# DM3370_PCIE_CLK.net
KiCad netlist of a schematic drawn in Altium Designer
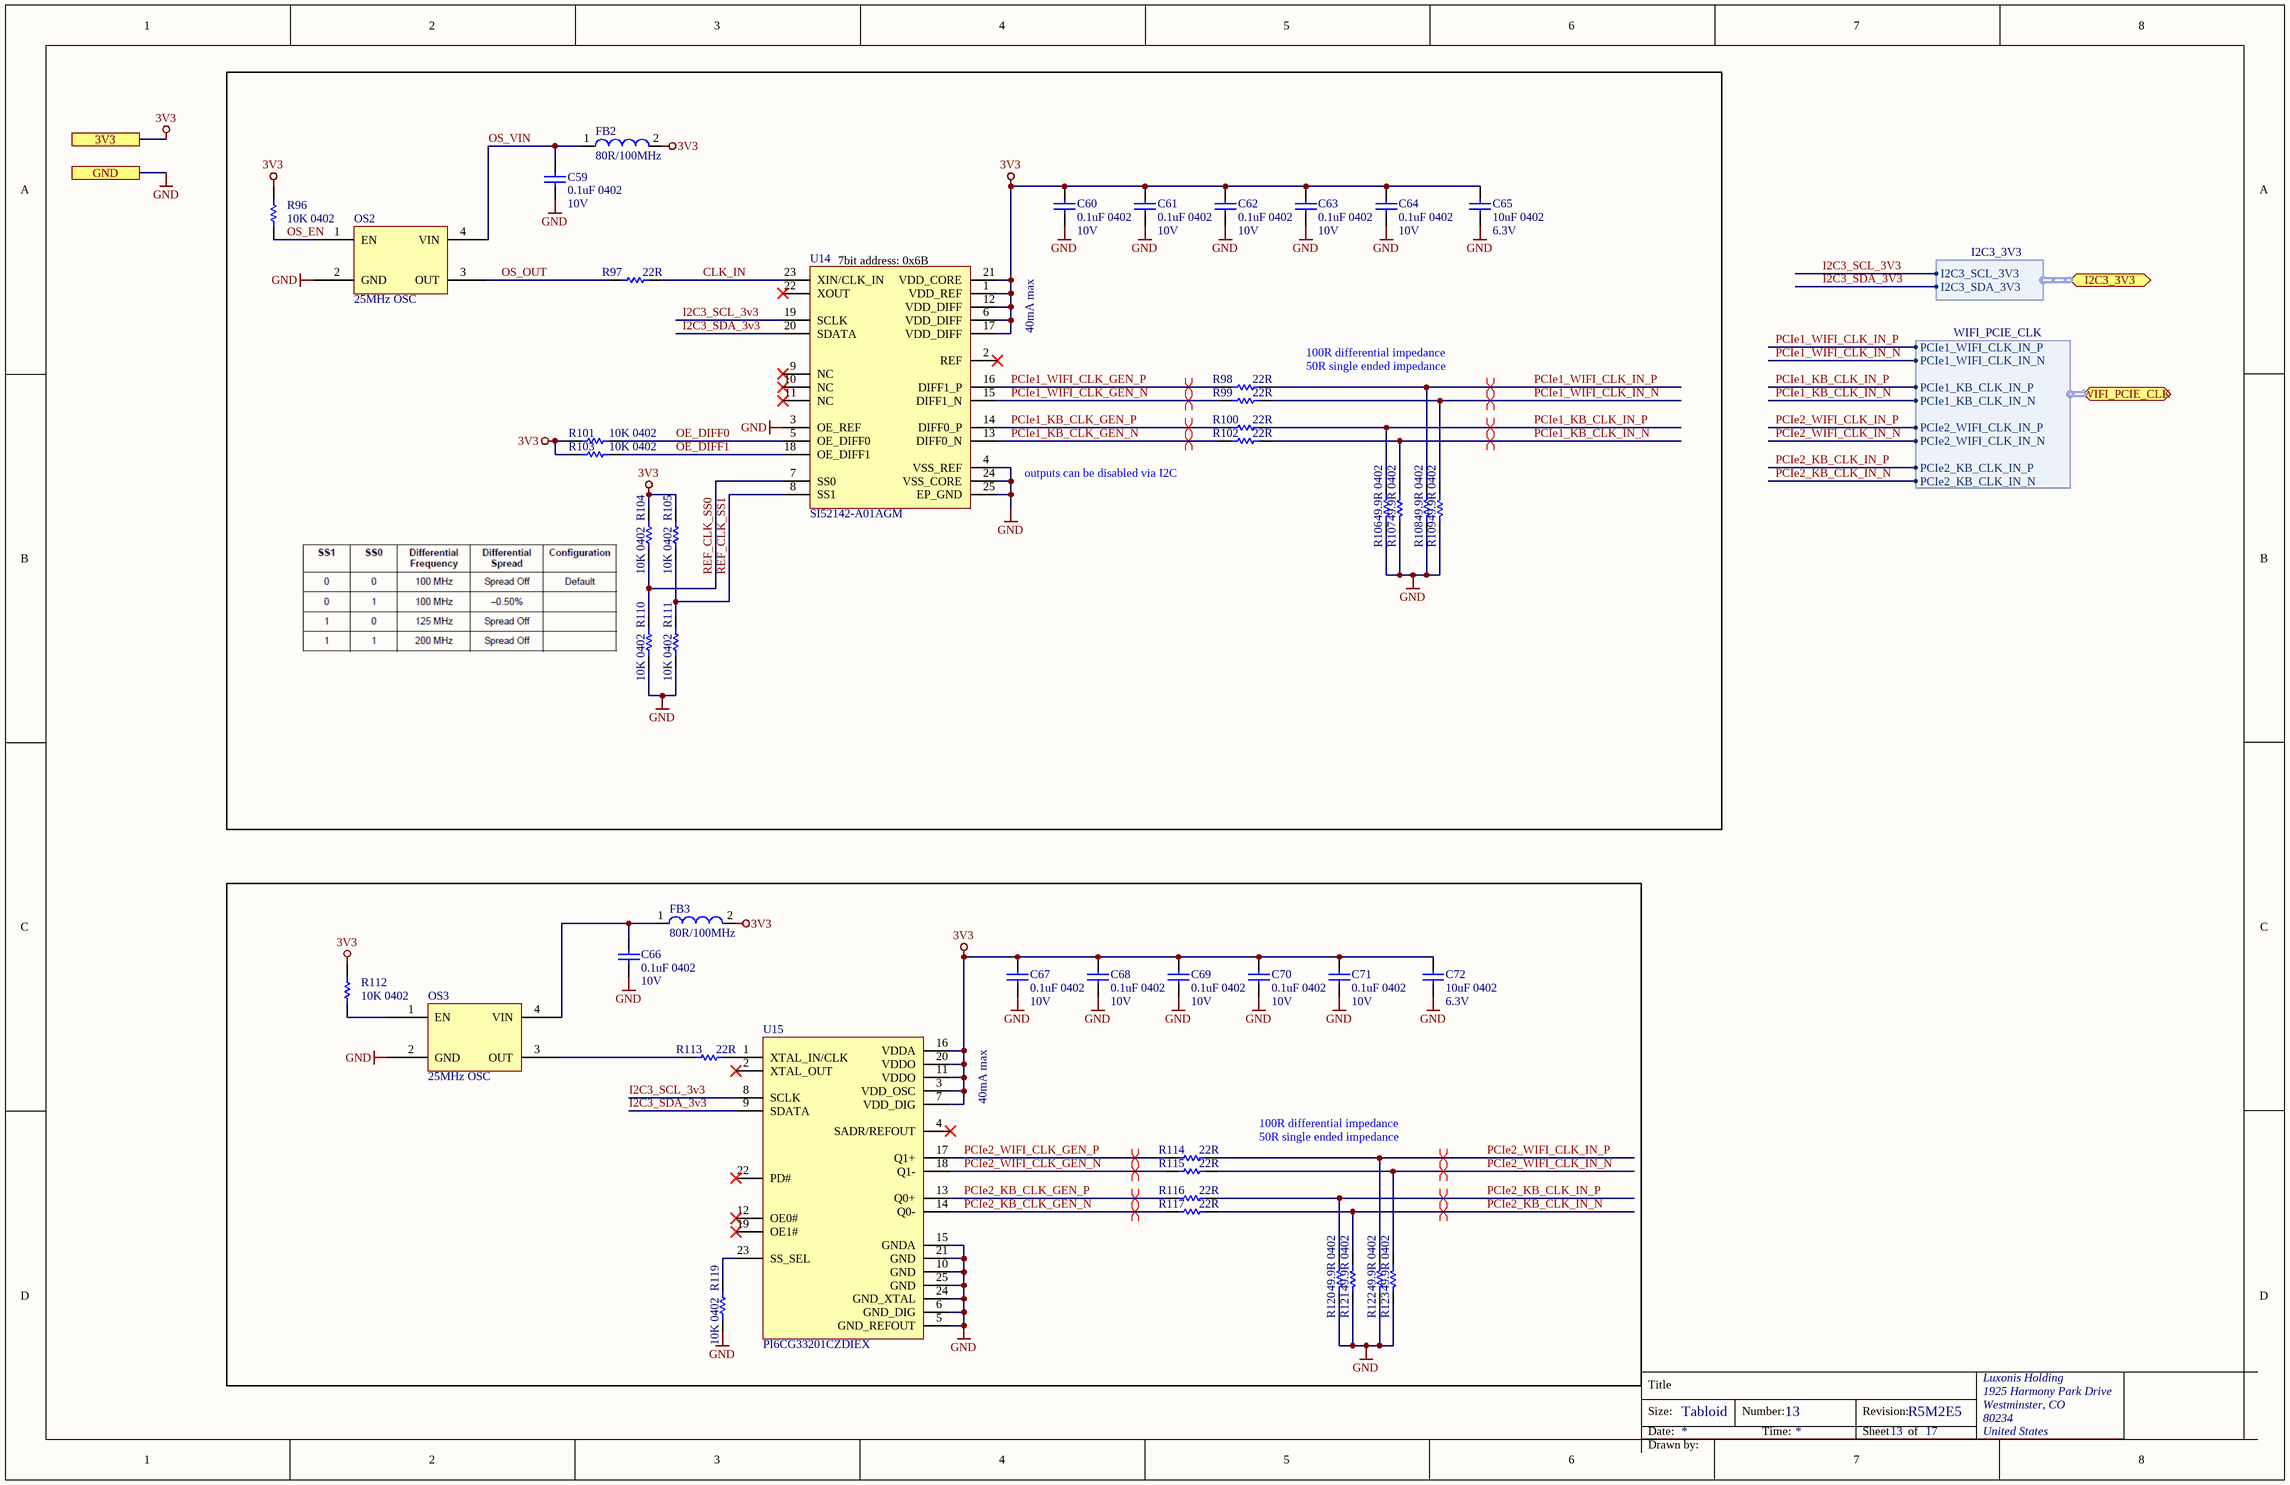
[diagram p0: DM3370_PCIE_CLK.SchDoc]

(export (version "E")
  (design (tool "Eeschema 10.0.6"))
  (components
    (comp (ref "C59")
      (value "0.1uF 0402")
      (footprint "CAP_Altium_Vault_Generic:CAPC0402(1005)70_L")
      (description "CAP CER 0.1UF 10V X7R 0402 5%")
      (fields (field (name "TOLERANCE") "5%") (field (name "VOLTAGE RATING") "10V"))
      (libsource (lib "LuxonisMaster") (part "GRM155R71A104JA01D"))
    )
    (comp (ref "C60")
      (value "0.1uF 0402")
      (footprint "CAP_Altium_Vault_Generic:CAPC0402(1005)70_L")
      (description "CAP CER 0.1UF 10V X7R 0402 5%")
      (fields (field (name "TOLERANCE") "5%") (field (name "VOLTAGE RATING") "10V"))
      (libsource (lib "LuxonisMaster") (part "GRM155R71A104JA01D"))
    )
    (comp (ref "C61")
      (value "0.1uF 0402")
      (footprint "CAP_Altium_Vault_Generic:CAPC0402(1005)70_L")
      (description "CAP CER 0.1UF 10V X7R 0402 5%")
      (fields (field (name "TOLERANCE") "5%") (field (name "VOLTAGE RATING") "10V"))
      (libsource (lib "LuxonisMaster") (part "GRM155R71A104JA01D"))
    )
    (comp (ref "C62")
      (value "0.1uF 0402")
      (footprint "CAP_Altium_Vault_Generic:CAPC0402(1005)70_L")
      (description "CAP CER 0.1UF 10V X7R 0402 5%")
      (fields (field (name "TOLERANCE") "5%") (field (name "VOLTAGE RATING") "10V"))
      (libsource (lib "LuxonisMaster") (part "GRM155R71A104JA01D"))
    )
    (comp (ref "C63")
      (value "0.1uF 0402")
      (footprint "CAP_Altium_Vault_Generic:CAPC0402(1005)70_L")
      (description "CAP CER 0.1UF 10V X7R 0402 5%")
      (fields (field (name "TOLERANCE") "5%") (field (name "VOLTAGE RATING") "10V"))
      (libsource (lib "LuxonisMaster") (part "GRM155R71A104JA01D"))
    )
    (comp (ref "C64")
      (value "0.1uF 0402")
      (footprint "CAP_Altium_Vault_Generic:CAPC0402(1005)70_L")
      (description "CAP CER 0.1UF 10V X7R 0402 5%")
      (fields (field (name "TOLERANCE") "5%") (field (name "VOLTAGE RATING") "10V"))
      (libsource (lib "LuxonisMaster") (part "GRM155R71A104JA01D"))
    )
    (comp (ref "C65")
      (value "10uF 0402")
      (footprint "CAP_Altium_Vault_Generic:CAPC0402(1005)70_L")
      (description "CAP CER 10UF 6.3V X5R 0402 20%")
      (fields (field (name "TOLERANCE") "20%") (field (name "VOLTAGE RATING") "6.3V"))
      (libsource (lib "LuxonisMaster") (part "GRM155R60J106ME15D"))
    )
    (comp (ref "C66")
      (value "0.1uF 0402")
      (footprint "CAP_Altium_Vault_Generic:CAPC0402(1005)70_L")
      (description "CAP CER 0.1UF 10V X7R 0402 5%")
      (fields (field (name "TOLERANCE") "5%") (field (name "VOLTAGE RATING") "10V"))
      (libsource (lib "LuxonisMaster") (part "GRM155R71A104JA01D"))
    )
    (comp (ref "C67")
      (value "0.1uF 0402")
      (footprint "CAP_Altium_Vault_Generic:CAPC0402(1005)70_L")
      (description "CAP CER 0.1UF 10V X7R 0402 5%")
      (fields (field (name "TOLERANCE") "5%") (field (name "VOLTAGE RATING") "10V"))
      (libsource (lib "LuxonisMaster") (part "GRM155R71A104JA01D"))
    )
    (comp (ref "C68")
      (value "0.1uF 0402")
      (footprint "CAP_Altium_Vault_Generic:CAPC0402(1005)70_L")
      (description "CAP CER 0.1UF 10V X7R 0402 5%")
      (fields (field (name "TOLERANCE") "5%") (field (name "VOLTAGE RATING") "10V"))
      (libsource (lib "LuxonisMaster") (part "GRM155R71A104JA01D"))
    )
    (comp (ref "C69")
      (value "0.1uF 0402")
      (footprint "CAP_Altium_Vault_Generic:CAPC0402(1005)70_L")
      (description "CAP CER 0.1UF 10V X7R 0402 5%")
      (fields (field (name "TOLERANCE") "5%") (field (name "VOLTAGE RATING") "10V"))
      (libsource (lib "LuxonisMaster") (part "GRM155R71A104JA01D"))
    )
    (comp (ref "C70")
      (value "0.1uF 0402")
      (footprint "CAP_Altium_Vault_Generic:CAPC0402(1005)70_L")
      (description "CAP CER 0.1UF 10V X7R 0402 5%")
      (fields (field (name "TOLERANCE") "5%") (field (name "VOLTAGE RATING") "10V"))
      (libsource (lib "LuxonisMaster") (part "GRM155R71A104JA01D"))
    )
    (comp (ref "C71")
      (value "0.1uF 0402")
      (footprint "CAP_Altium_Vault_Generic:CAPC0402(1005)70_L")
      (description "CAP CER 0.1UF 10V X7R 0402 5%")
      (fields (field (name "TOLERANCE") "5%") (field (name "VOLTAGE RATING") "10V"))
      (libsource (lib "LuxonisMaster") (part "GRM155R71A104JA01D"))
    )
    (comp (ref "C72")
      (value "10uF 0402")
      (footprint "CAP_Altium_Vault_Generic:CAPC0402(1005)70_L")
      (description "CAP CER 10UF 6.3V X5R 0402 20%")
      (fields (field (name "TOLERANCE") "20%") (field (name "VOLTAGE RATING") "6.3V"))
      (libsource (lib "LuxonisMaster") (part "GRM155R60J106ME15D"))
    )
    (comp (ref "FB2")
      (value "80R/100MHz")
      (footprint "LuxonisMaster:BK1608HS800-T_L")
      (description "FERRITE BEAD 80 OHM 0603 1LN")
      (fields (field (name "TOLERANCE") "25%"))
      (libsource (lib "LuxonisMaster") (part "BK1608HS800-T"))
    )
    (comp (ref "FB3")
      (value "80R/100MHz")
      (footprint "LuxonisMaster:BK1608HS800-T_L")
      (description "FERRITE BEAD 80 OHM 0603 1LN")
      (fields (field (name "TOLERANCE") "25%"))
      (libsource (lib "LuxonisMaster") (part "BK1608HS800-T"))
    )
    (comp (ref "OS2")
      (value "25MHz OSC")
      (footprint "2520_OSC(FJ2400002)")
      (description "MEMS OSC XO 25.0000MHZ LVCMOS")
      (libsource (lib "LuxonisMaster") (part "ASDMB-25.000MHZ-LC-T"))
    )
    (comp (ref "OS3")
      (value "25MHz OSC")
      (footprint "2520_OSC(FJ2400002)")
      (description "MEMS OSC XO 25.0000MHZ LVCMOS")
      (libsource (lib "LuxonisMaster") (part "ASDMB-25.000MHZ-LC-T"))
    )
    (comp (ref "R96")
      (value "10K 0402")
      (footprint "RES_Altium_Vault_Generic:RESC0402(1005)_L")
      (fields (field (name "TOLERANCE") "1%"))
      (libsource (lib "LuxonisMaster") (part "RC0402FR-1310KL"))
    )
    (comp (ref "R97")
      (value "RC0402FR-0722RL")
      (footprint "RESC0402(1005)_L")
      (description "RES SMD 22 OHM 1% 1/16W 0402")
      (fields (field (name "TOLERANCE") "1%") (field (name "RESISTANCE") "22R"))
      (libsource (lib "Luxonis LLC") (part "CR0402-FX-2492GLF"))
    )
    (comp (ref "R98")
      (value "RC0402FR-0722RL")
      (footprint "RESC0402(1005)_L")
      (description "RES SMD 22 OHM 1% 1/16W 0402")
      (fields (field (name "TOLERANCE") "1%") (field (name "RESISTANCE") "22R"))
      (libsource (lib "Luxonis LLC") (part "CR0402-FX-2492GLF"))
    )
    (comp (ref "R99")
      (value "RC0402FR-0722RL")
      (footprint "RESC0402(1005)_L")
      (description "RES SMD 22 OHM 1% 1/16W 0402")
      (fields (field (name "TOLERANCE") "1%") (field (name "RESISTANCE") "22R"))
      (libsource (lib "Luxonis LLC") (part "CR0402-FX-2492GLF"))
    )
    (comp (ref "R100")
      (value "RC0402FR-0722RL")
      (footprint "RESC0402(1005)_L")
      (description "RES SMD 22 OHM 1% 1/16W 0402")
      (fields (field (name "TOLERANCE") "1%") (field (name "RESISTANCE") "22R"))
      (libsource (lib "Luxonis LLC") (part "CR0402-FX-2492GLF"))
    )
    (comp (ref "R101")
      (value "10K 0402")
      (footprint "RES_Altium_Vault_Generic:RESC0402(1005)_L")
      (fields (field (name "TOLERANCE") "1%"))
      (libsource (lib "LuxonisMaster") (part "RC0402FR-1310KL"))
    )
    (comp (ref "R102")
      (value "RC0402FR-0722RL")
      (footprint "RESC0402(1005)_L")
      (description "RES SMD 22 OHM 1% 1/16W 0402")
      (fields (field (name "TOLERANCE") "1%") (field (name "RESISTANCE") "22R"))
      (libsource (lib "Luxonis LLC") (part "CR0402-FX-2492GLF"))
    )
    (comp (ref "R103")
      (value "10K 0402")
      (footprint "RES_Altium_Vault_Generic:RESC0402(1005)_L")
      (fields (field (name "TOLERANCE") "1%"))
      (libsource (lib "LuxonisMaster") (part "RC0402FR-1310KL"))
    )
    (comp (ref "R104")
      (value "10K 0402")
      (footprint "RES_Altium_Vault_Generic:RESC0402(1005)_L")
      (fields (field (name "TOLERANCE") "1%"))
      (libsource (lib "LuxonisMaster") (part "RC0402FR-1310KL"))
    )
    (comp (ref "R105")
      (value "10K 0402")
      (footprint "RES_Altium_Vault_Generic:RESC0402(1005)_L")
      (fields (field (name "TOLERANCE") "1%"))
      (libsource (lib "LuxonisMaster") (part "RC0402FR-1310KL"))
    )
    (comp (ref "R106")
      (value "49.9R 0402")
      (footprint "RES_Altium_Vault_Generic:RESC0402(1005)_L")
      (description "RES SMD 49.9 OHM 1% 1/16W 0402")
      (fields (field (name "TOLERANCE") "1%"))
      (libsource (lib "LuxonisMaster") (part "RC0402FR-0749R9L"))
    )
    (comp (ref "R107")
      (value "49.9R 0402")
      (footprint "RES_Altium_Vault_Generic:RESC0402(1005)_L")
      (description "RES SMD 49.9 OHM 1% 1/16W 0402")
      (fields (field (name "TOLERANCE") "1%"))
      (libsource (lib "LuxonisMaster") (part "RC0402FR-0749R9L"))
    )
    (comp (ref "R108")
      (value "49.9R 0402")
      (footprint "RES_Altium_Vault_Generic:RESC0402(1005)_L")
      (description "RES SMD 49.9 OHM 1% 1/16W 0402")
      (fields (field (name "TOLERANCE") "1%"))
      (libsource (lib "LuxonisMaster") (part "RC0402FR-0749R9L"))
    )
    (comp (ref "R109")
      (value "49.9R 0402")
      (footprint "RES_Altium_Vault_Generic:RESC0402(1005)_L")
      (description "RES SMD 49.9 OHM 1% 1/16W 0402")
      (fields (field (name "TOLERANCE") "1%"))
      (libsource (lib "LuxonisMaster") (part "RC0402FR-0749R9L"))
    )
    (comp (ref "R110")
      (value "10K 0402")
      (footprint "RES_Altium_Vault_Generic:RESC0402(1005)_L")
      (fields (field (name "TOLERANCE") "1%"))
      (libsource (lib "LuxonisMaster") (part "RC0402FR-1310KL"))
    )
    (comp (ref "R111")
      (value "10K 0402")
      (footprint "RES_Altium_Vault_Generic:RESC0402(1005)_L")
      (fields (field (name "TOLERANCE") "1%"))
      (libsource (lib "LuxonisMaster") (part "RC0402FR-1310KL"))
    )
    (comp (ref "R112")
      (value "10K 0402")
      (footprint "RES_Altium_Vault_Generic:RESC0402(1005)_L")
      (fields (field (name "TOLERANCE") "1%"))
      (libsource (lib "LuxonisMaster") (part "RC0402FR-1310KL"))
    )
    (comp (ref "R113")
      (value "RC0402FR-0722RL")
      (footprint "RESC0402(1005)_L")
      (description "RES SMD 22 OHM 1% 1/16W 0402")
      (fields (field (name "TOLERANCE") "1%") (field (name "RESISTANCE") "22R"))
      (libsource (lib "Luxonis LLC") (part "CR0402-FX-2492GLF"))
    )
    (comp (ref "R114")
      (value "RC0402FR-0722RL")
      (footprint "RESC0402(1005)_L")
      (description "RES SMD 22 OHM 1% 1/16W 0402")
      (fields (field (name "TOLERANCE") "1%") (field (name "RESISTANCE") "22R"))
      (libsource (lib "Luxonis LLC") (part "CR0402-FX-2492GLF"))
    )
    (comp (ref "R115")
      (value "RC0402FR-0722RL")
      (footprint "RESC0402(1005)_L")
      (description "RES SMD 22 OHM 1% 1/16W 0402")
      (fields (field (name "TOLERANCE") "1%") (field (name "RESISTANCE") "22R"))
      (libsource (lib "Luxonis LLC") (part "CR0402-FX-2492GLF"))
    )
    (comp (ref "R116")
      (value "RC0402FR-0722RL")
      (footprint "RESC0402(1005)_L")
      (description "RES SMD 22 OHM 1% 1/16W 0402")
      (fields (field (name "TOLERANCE") "1%") (field (name "RESISTANCE") "22R"))
      (libsource (lib "Luxonis LLC") (part "CR0402-FX-2492GLF"))
    )
    (comp (ref "R117")
      (value "RC0402FR-0722RL")
      (footprint "RESC0402(1005)_L")
      (description "RES SMD 22 OHM 1% 1/16W 0402")
      (fields (field (name "TOLERANCE") "1%") (field (name "RESISTANCE") "22R"))
      (libsource (lib "Luxonis LLC") (part "CR0402-FX-2492GLF"))
    )
    (comp (ref "R119")
      (value "10K 0402")
      (footprint "RES_Altium_Vault_Generic:RESC0402(1005)_L")
      (fields (field (name "TOLERANCE") "1%"))
      (libsource (lib "LuxonisMaster") (part "RC0402FR-1310KL"))
    )
    (comp (ref "R120")
      (value "49.9R 0402")
      (footprint "RES_Altium_Vault_Generic:RESC0402(1005)_L")
      (description "RES SMD 49.9 OHM 1% 1/16W 0402")
      (fields (field (name "TOLERANCE") "1%"))
      (libsource (lib "LuxonisMaster") (part "RC0402FR-0749R9L"))
    )
    (comp (ref "R121")
      (value "49.9R 0402")
      (footprint "RES_Altium_Vault_Generic:RESC0402(1005)_L")
      (description "RES SMD 49.9 OHM 1% 1/16W 0402")
      (fields (field (name "TOLERANCE") "1%"))
      (libsource (lib "LuxonisMaster") (part "RC0402FR-0749R9L"))
    )
    (comp (ref "R122")
      (value "49.9R 0402")
      (footprint "RES_Altium_Vault_Generic:RESC0402(1005)_L")
      (description "RES SMD 49.9 OHM 1% 1/16W 0402")
      (fields (field (name "TOLERANCE") "1%"))
      (libsource (lib "LuxonisMaster") (part "RC0402FR-0749R9L"))
    )
    (comp (ref "R123")
      (value "49.9R 0402")
      (footprint "RES_Altium_Vault_Generic:RESC0402(1005)_L")
      (description "RES SMD 49.9 OHM 1% 1/16W 0402")
      (fields (field (name "TOLERANCE") "1%"))
      (libsource (lib "LuxonisMaster") (part "RC0402FR-0749R9L"))
    )
    (comp (ref "U14")
      (value "SI52142-A01AGM")
      (footprint "SI52142-A01AGM")
      (description "IC CLK GENERATOR 200MHZ 24QFN")
      (libsource (lib "Luxonis LLC") (part "SI52142-A01AGM"))
    )
    (comp (ref "U15")
      (value "PI6CG33201CZDIEX")
      (footprint "PI6CG33201CZDIEX")
      (description "Clock Generator V-QFN4040-24 T&r 3.5K")
      (libsource (lib "Luxonis LLC") (part "PI6CG33201CZDIEX"))
    )
  )
  (nets
    (net (code "3") (name "/CLK_IN") (class "Default")
      (node (ref "R97") (pin "2") (pinfunction "2_2") (pintype "passive"))
      (node (ref "U14") (pin "23") (pinfunction "XIN/CLK_IN_23") (pintype "passive"))
    )
    (net (code "5") (name "/I2C3_SCL_3v3") (class "Default")
      (node (ref "U14") (pin "19") (pinfunction "SCLK_19") (pintype "passive"))
      (node (ref "U15") (pin "8") (pinfunction "SCLK_8") (pintype "passive"))
    )
    (net (code "7") (name "/I2C3_SDA_3v3") (class "Default")
      (node (ref "U14") (pin "20") (pinfunction "SDATA_20") (pintype "passive"))
      (node (ref "U15") (pin "9") (pinfunction "SDATA_9") (pintype "passive"))
    )
    (net (code "8") (name "/OE_DIFF0") (class "Default")
      (node (ref "R101") (pin "2") (pinfunction "2_2") (pintype "passive"))
      (node (ref "U14") (pin "5") (pinfunction "OE_DIFF0_5") (pintype "passive"))
    )
    (net (code "9") (name "/OE_DIFF1") (class "Default")
      (node (ref "R103") (pin "2") (pinfunction "2_2") (pintype "passive"))
      (node (ref "U14") (pin "18") (pinfunction "OE_DIFF1_18") (pintype "passive"))
    )
    (net (code "10") (name "/OS_EN") (class "Default")
      (node (ref "OS2") (pin "1") (pinfunction "EN_1") (pintype "passive"))
      (node (ref "R96") (pin "1") (pinfunction "1_1") (pintype "passive"))
    )
    (net (code "11") (name "/OS_OUT") (class "Default")
      (node (ref "OS2") (pin "3") (pinfunction "OUT_3") (pintype "passive"))
      (node (ref "R97") (pin "1") (pinfunction "1_1") (pintype "passive"))
    )
    (net (code "12") (name "/OS_VIN") (class "Default")
      (node (ref "C59") (pin "1") (pinfunction "1_1") (pintype "passive"))
      (node (ref "FB2") (pin "1") (pinfunction "1_1") (pintype "passive"))
      (node (ref "OS2") (pin "4") (pinfunction "VIN_4") (pintype "passive"))
    )
    (net (code "13") (name "/PCIe1_KB_CLK_GEN_N") (class "Default")
      (node (ref "R102") (pin "1") (pinfunction "1_1") (pintype "passive"))
      (node (ref "U14") (pin "13") (pinfunction "DIFF0_N_13") (pintype "passive"))
    )
    (net (code "14") (name "/PCIe1_KB_CLK_GEN_P") (class "Default")
      (node (ref "R100") (pin "1") (pinfunction "1_1") (pintype "passive"))
      (node (ref "U14") (pin "14") (pinfunction "DIFF0_P_14") (pintype "passive"))
    )
    (net (code "15") (name "/PCIe1_KB_CLK_IN_N") (class "Default")
      (node (ref "R102") (pin "2") (pinfunction "2_2") (pintype "passive"))
      (node (ref "R107") (pin "2") (pinfunction "2_2") (pintype "passive"))
    )
    (net (code "16") (name "/PCIe1_KB_CLK_IN_P") (class "Default")
      (node (ref "R100") (pin "2") (pinfunction "2_2") (pintype "passive"))
      (node (ref "R106") (pin "1") (pinfunction "1_1") (pintype "passive"))
    )
    (net (code "17") (name "/PCIe1_WIFI_CLK_GEN_N") (class "Default")
      (node (ref "R99") (pin "1") (pinfunction "1_1") (pintype "passive"))
      (node (ref "U14") (pin "15") (pinfunction "DIFF1_N_15") (pintype "passive"))
    )
    (net (code "18") (name "/PCIe1_WIFI_CLK_GEN_P") (class "Default")
      (node (ref "R98") (pin "1") (pinfunction "1_1") (pintype "passive"))
      (node (ref "U14") (pin "16") (pinfunction "DIFF1_P_16") (pintype "passive"))
    )
    (net (code "19") (name "/PCIe1_WIFI_CLK_IN_N") (class "Default")
      (node (ref "R109") (pin "2") (pinfunction "2_2") (pintype "passive"))
      (node (ref "R99") (pin "2") (pinfunction "2_2") (pintype "passive"))
    )
    (net (code "20") (name "/PCIe1_WIFI_CLK_IN_P") (class "Default")
      (node (ref "R108") (pin "2") (pinfunction "2_2") (pintype "passive"))
      (node (ref "R98") (pin "2") (pinfunction "2_2") (pintype "passive"))
    )
    (net (code "21") (name "/PCIe2_KB_CLK_GEN_N") (class "Default")
      (node (ref "R117") (pin "1") (pinfunction "1_1") (pintype "passive"))
      (node (ref "U15") (pin "14") (pinfunction "Q0-_14") (pintype "passive"))
    )
    (net (code "22") (name "/PCIe2_KB_CLK_GEN_P") (class "Default")
      (node (ref "R116") (pin "1") (pinfunction "1_1") (pintype "passive"))
      (node (ref "U15") (pin "13") (pinfunction "Q0+_13") (pintype "passive"))
    )
    (net (code "23") (name "/PCIe2_KB_CLK_IN_N") (class "Default")
      (node (ref "R117") (pin "2") (pinfunction "2_2") (pintype "passive"))
      (node (ref "R121") (pin "2") (pinfunction "2_2") (pintype "passive"))
    )
    (net (code "24") (name "/PCIe2_KB_CLK_IN_P") (class "Default")
      (node (ref "R116") (pin "2") (pinfunction "2_2") (pintype "passive"))
      (node (ref "R120") (pin "1") (pinfunction "1_1") (pintype "passive"))
    )
    (net (code "25") (name "/PCIe2_WIFI_CLK_GEN_N") (class "Default")
      (node (ref "R115") (pin "1") (pinfunction "1_1") (pintype "passive"))
      (node (ref "U15") (pin "18") (pinfunction "Q1-_18") (pintype "passive"))
    )
    (net (code "26") (name "/PCIe2_WIFI_CLK_GEN_P") (class "Default")
      (node (ref "R114") (pin "1") (pinfunction "1_1") (pintype "passive"))
      (node (ref "U15") (pin "17") (pinfunction "Q1+_17") (pintype "passive"))
    )
    (net (code "27") (name "/PCIe2_WIFI_CLK_IN_N") (class "Default")
      (node (ref "R115") (pin "2") (pinfunction "2_2") (pintype "passive"))
      (node (ref "R123") (pin "2") (pinfunction "2_2") (pintype "passive"))
    )
    (net (code "28") (name "/PCIe2_WIFI_CLK_IN_P") (class "Default")
      (node (ref "R114") (pin "2") (pinfunction "2_2") (pintype "passive"))
      (node (ref "R122") (pin "2") (pinfunction "2_2") (pintype "passive"))
    )
    (net (code "29") (name "/REF_CLK_SS0") (class "Default")
      (node (ref "R104") (pin "2") (pinfunction "2_2") (pintype "passive"))
      (node (ref "R110") (pin "1") (pinfunction "1_1") (pintype "passive"))
      (node (ref "U14") (pin "7") (pinfunction "SS0_7") (pintype "passive"))
    )
    (net (code "30") (name "/REF_CLK_SS1") (class "Default")
      (node (ref "R105") (pin "2") (pinfunction "2_2") (pintype "passive"))
      (node (ref "R111") (pin "1") (pinfunction "1_1") (pintype "passive"))
      (node (ref "U14") (pin "8") (pinfunction "SS1_8") (pintype "passive"))
    )
    (net (code "33") (name "3V3") (class "Default")
      (node (ref "C60") (pin "1") (pinfunction "1_1") (pintype "passive"))
      (node (ref "C61") (pin "1") (pinfunction "1_1") (pintype "passive"))
      (node (ref "C62") (pin "1") (pinfunction "1_1") (pintype "passive"))
      (node (ref "C63") (pin "1") (pinfunction "1_1") (pintype "passive"))
      (node (ref "C64") (pin "1") (pinfunction "1_1") (pintype "passive"))
      (node (ref "C65") (pin "2") (pinfunction "2_2") (pintype "passive"))
      (node (ref "C67") (pin "1") (pinfunction "1_1") (pintype "passive"))
      (node (ref "C68") (pin "1") (pinfunction "1_1") (pintype "passive"))
      (node (ref "C69") (pin "1") (pinfunction "1_1") (pintype "passive"))
      (node (ref "C70") (pin "1") (pinfunction "1_1") (pintype "passive"))
      (node (ref "C71") (pin "1") (pinfunction "1_1") (pintype "passive"))
      (node (ref "C72") (pin "2") (pinfunction "2_2") (pintype "passive"))
      (node (ref "FB2") (pin "2") (pinfunction "2_2") (pintype "passive"))
      (node (ref "FB3") (pin "2") (pinfunction "2_2") (pintype "passive"))
      (node (ref "R101") (pin "1") (pinfunction "1_1") (pintype "passive"))
      (node (ref "R103") (pin "1") (pinfunction "1_1") (pintype "passive"))
      (node (ref "R104") (pin "1") (pinfunction "1_1") (pintype "passive"))
      (node (ref "R105") (pin "1") (pinfunction "1_1") (pintype "passive"))
      (node (ref "R112") (pin "2") (pinfunction "2_2") (pintype "passive"))
      (node (ref "R96") (pin "2") (pinfunction "2_2") (pintype "passive"))
      (node (ref "U14") (pin "1") (pinfunction "VDD_REF_1") (pintype "passive"))
      (node (ref "U14") (pin "12") (pinfunction "VDD_DIFF_12") (pintype "passive"))
      (node (ref "U14") (pin "17") (pinfunction "VDD_DIFF_17") (pintype "passive"))
      (node (ref "U14") (pin "21") (pinfunction "VDD_CORE_21") (pintype "passive"))
      (node (ref "U14") (pin "6") (pinfunction "VDD_DIFF_6") (pintype "passive"))
      (node (ref "U15") (pin "11") (pinfunction "VDDO_11") (pintype "passive"))
      (node (ref "U15") (pin "16") (pinfunction "VDDA_16") (pintype "passive"))
      (node (ref "U15") (pin "20") (pinfunction "VDDO_20") (pintype "passive"))
      (node (ref "U15") (pin "3") (pinfunction "VDD_OSC_3") (pintype "passive"))
      (node (ref "U15") (pin "7") (pinfunction "VDD_DIG_7") (pintype "passive"))
    )
    (net (code "34") (name "GND") (class "Default")
      (node (ref "C59") (pin "2") (pinfunction "2_2") (pintype "passive"))
      (node (ref "C60") (pin "2") (pinfunction "2_2") (pintype "passive"))
      (node (ref "C61") (pin "2") (pinfunction "2_2") (pintype "passive"))
      (node (ref "C62") (pin "2") (pinfunction "2_2") (pintype "passive"))
      (node (ref "C63") (pin "2") (pinfunction "2_2") (pintype "passive"))
      (node (ref "C64") (pin "2") (pinfunction "2_2") (pintype "passive"))
      (node (ref "C65") (pin "1") (pinfunction "1_1") (pintype "passive"))
      (node (ref "C66") (pin "2") (pinfunction "2_2") (pintype "passive"))
      (node (ref "C67") (pin "2") (pinfunction "2_2") (pintype "passive"))
      (node (ref "C68") (pin "2") (pinfunction "2_2") (pintype "passive"))
      (node (ref "C69") (pin "2") (pinfunction "2_2") (pintype "passive"))
      (node (ref "C70") (pin "2") (pinfunction "2_2") (pintype "passive"))
      (node (ref "C71") (pin "2") (pinfunction "2_2") (pintype "passive"))
      (node (ref "C72") (pin "1") (pinfunction "1_1") (pintype "passive"))
      (node (ref "OS2") (pin "2") (pinfunction "GND_2") (pintype "passive"))
      (node (ref "OS3") (pin "2") (pinfunction "GND_2") (pintype "passive"))
      (node (ref "R106") (pin "2") (pinfunction "2_2") (pintype "passive"))
      (node (ref "R107") (pin "1") (pinfunction "1_1") (pintype "passive"))
      (node (ref "R108") (pin "1") (pinfunction "1_1") (pintype "passive"))
      (node (ref "R109") (pin "1") (pinfunction "1_1") (pintype "passive"))
      (node (ref "R110") (pin "2") (pinfunction "2_2") (pintype "passive"))
      (node (ref "R111") (pin "2") (pinfunction "2_2") (pintype "passive"))
      (node (ref "R119") (pin "2") (pinfunction "2_2") (pintype "passive"))
      (node (ref "R120") (pin "2") (pinfunction "2_2") (pintype "passive"))
      (node (ref "R121") (pin "1") (pinfunction "1_1") (pintype "passive"))
      (node (ref "R122") (pin "1") (pinfunction "1_1") (pintype "passive"))
      (node (ref "R123") (pin "1") (pinfunction "1_1") (pintype "passive"))
      (node (ref "U14") (pin "24") (pinfunction "VSS_CORE_24") (pintype "passive"))
      (node (ref "U14") (pin "25") (pinfunction "EP_GND_25") (pintype "passive"))
      (node (ref "U14") (pin "3") (pinfunction "OE_REF_3") (pintype "passive"))
      (node (ref "U14") (pin "4") (pinfunction "VSS_REF_4") (pintype "passive"))
      (node (ref "U15") (pin "10") (pinfunction "GND_10") (pintype "passive"))
      (node (ref "U15") (pin "15") (pinfunction "GNDA_15") (pintype "passive"))
      (node (ref "U15") (pin "21") (pinfunction "GND_21") (pintype "passive"))
      (node (ref "U15") (pin "24") (pinfunction "GND_XTAL_24") (pintype "passive"))
      (node (ref "U15") (pin "25") (pinfunction "GND_25") (pintype "passive"))
      (node (ref "U15") (pin "5") (pinfunction "GND_REFOUT_5") (pintype "passive"))
      (node (ref "U15") (pin "6") (pinfunction "GND_DIG_6") (pintype "passive"))
    )
    (net (code "35") (name "Net-(OS3-EN)") (class "Default")
      (node (ref "OS3") (pin "1") (pinfunction "EN_1") (pintype "passive"))
      (node (ref "R112") (pin "1") (pinfunction "1_1") (pintype "passive"))
    )
    (net (code "36") (name "Net-(OS3-OUT)") (class "Default")
      (node (ref "OS3") (pin "3") (pinfunction "OUT_3") (pintype "passive"))
      (node (ref "R113") (pin "1") (pinfunction "1_1") (pintype "passive"))
    )
    (net (code "37") (name "Net-(OS3-VIN)") (class "Default")
      (node (ref "C66") (pin "1") (pinfunction "1_1") (pintype "passive"))
      (node (ref "FB3") (pin "1") (pinfunction "1_1") (pintype "passive"))
      (node (ref "OS3") (pin "4") (pinfunction "VIN_4") (pintype "passive"))
    )
    (net (code "38") (name "Net-(U15-SS_SEL)") (class "Default")
      (node (ref "R119") (pin "1") (pinfunction "1_1") (pintype "passive"))
      (node (ref "U15") (pin "23") (pinfunction "SS_SEL_23") (pintype "passive"))
    )
    (net (code "39") (name "Net-(U15-XTAL_IN{slash}CLK)") (class "Default")
      (node (ref "R113") (pin "2") (pinfunction "2_2") (pintype "passive"))
      (node (ref "U15") (pin "1") (pinfunction "XTAL_IN/CLK_1") (pintype "passive"))
    )
    (net (code "40") (name "unconnected-(U14-NC-Pad9)") (class "Default")
      (node (ref "U14") (pin "9") (pinfunction "NC_9") (pintype "passive+no_connect"))
    )
    (net (code "41") (name "unconnected-(U14-NC-Pad10)") (class "Default")
      (node (ref "U14") (pin "10") (pinfunction "NC_10") (pintype "passive+no_connect"))
    )
    (net (code "42") (name "unconnected-(U14-NC-Pad11)") (class "Default")
      (node (ref "U14") (pin "11") (pinfunction "NC_11") (pintype "passive+no_connect"))
    )
    (net (code "43") (name "unconnected-(U14-REF-Pad2)") (class "Default")
      (node (ref "U14") (pin "2") (pinfunction "REF_2") (pintype "passive+no_connect"))
    )
    (net (code "44") (name "unconnected-(U14-XOUT-Pad22)") (class "Default")
      (node (ref "U14") (pin "22") (pinfunction "XOUT_22") (pintype "passive+no_connect"))
    )
    (net (code "45") (name "unconnected-(U15-OE0#-Pad12)") (class "Default")
      (node (ref "U15") (pin "12") (pinfunction "OE0#_12") (pintype "passive+no_connect"))
    )
    (net (code "46") (name "unconnected-(U15-OE1#-Pad19)") (class "Default")
      (node (ref "U15") (pin "19") (pinfunction "OE1#_19") (pintype "passive+no_connect"))
    )
    (net (code "47") (name "unconnected-(U15-PD#-Pad22)") (class "Default")
      (node (ref "U15") (pin "22") (pinfunction "PD#_22") (pintype "passive+no_connect"))
    )
    (net (code "48") (name "unconnected-(U15-SADR{slash}REFOUT-Pad4)") (class "Default")
      (node (ref "U15") (pin "4") (pinfunction "SADR/REFOUT_4") (pintype "passive+no_connect"))
    )
    (net (code "49") (name "unconnected-(U15-XTAL_OUT-Pad2)") (class "Default")
      (node (ref "U15") (pin "2") (pinfunction "XTAL_OUT_2") (pintype "passive+no_connect"))
    )
  )
)
